# Bryan.net
KiCad netlist of a schematic drawn in EAGLE
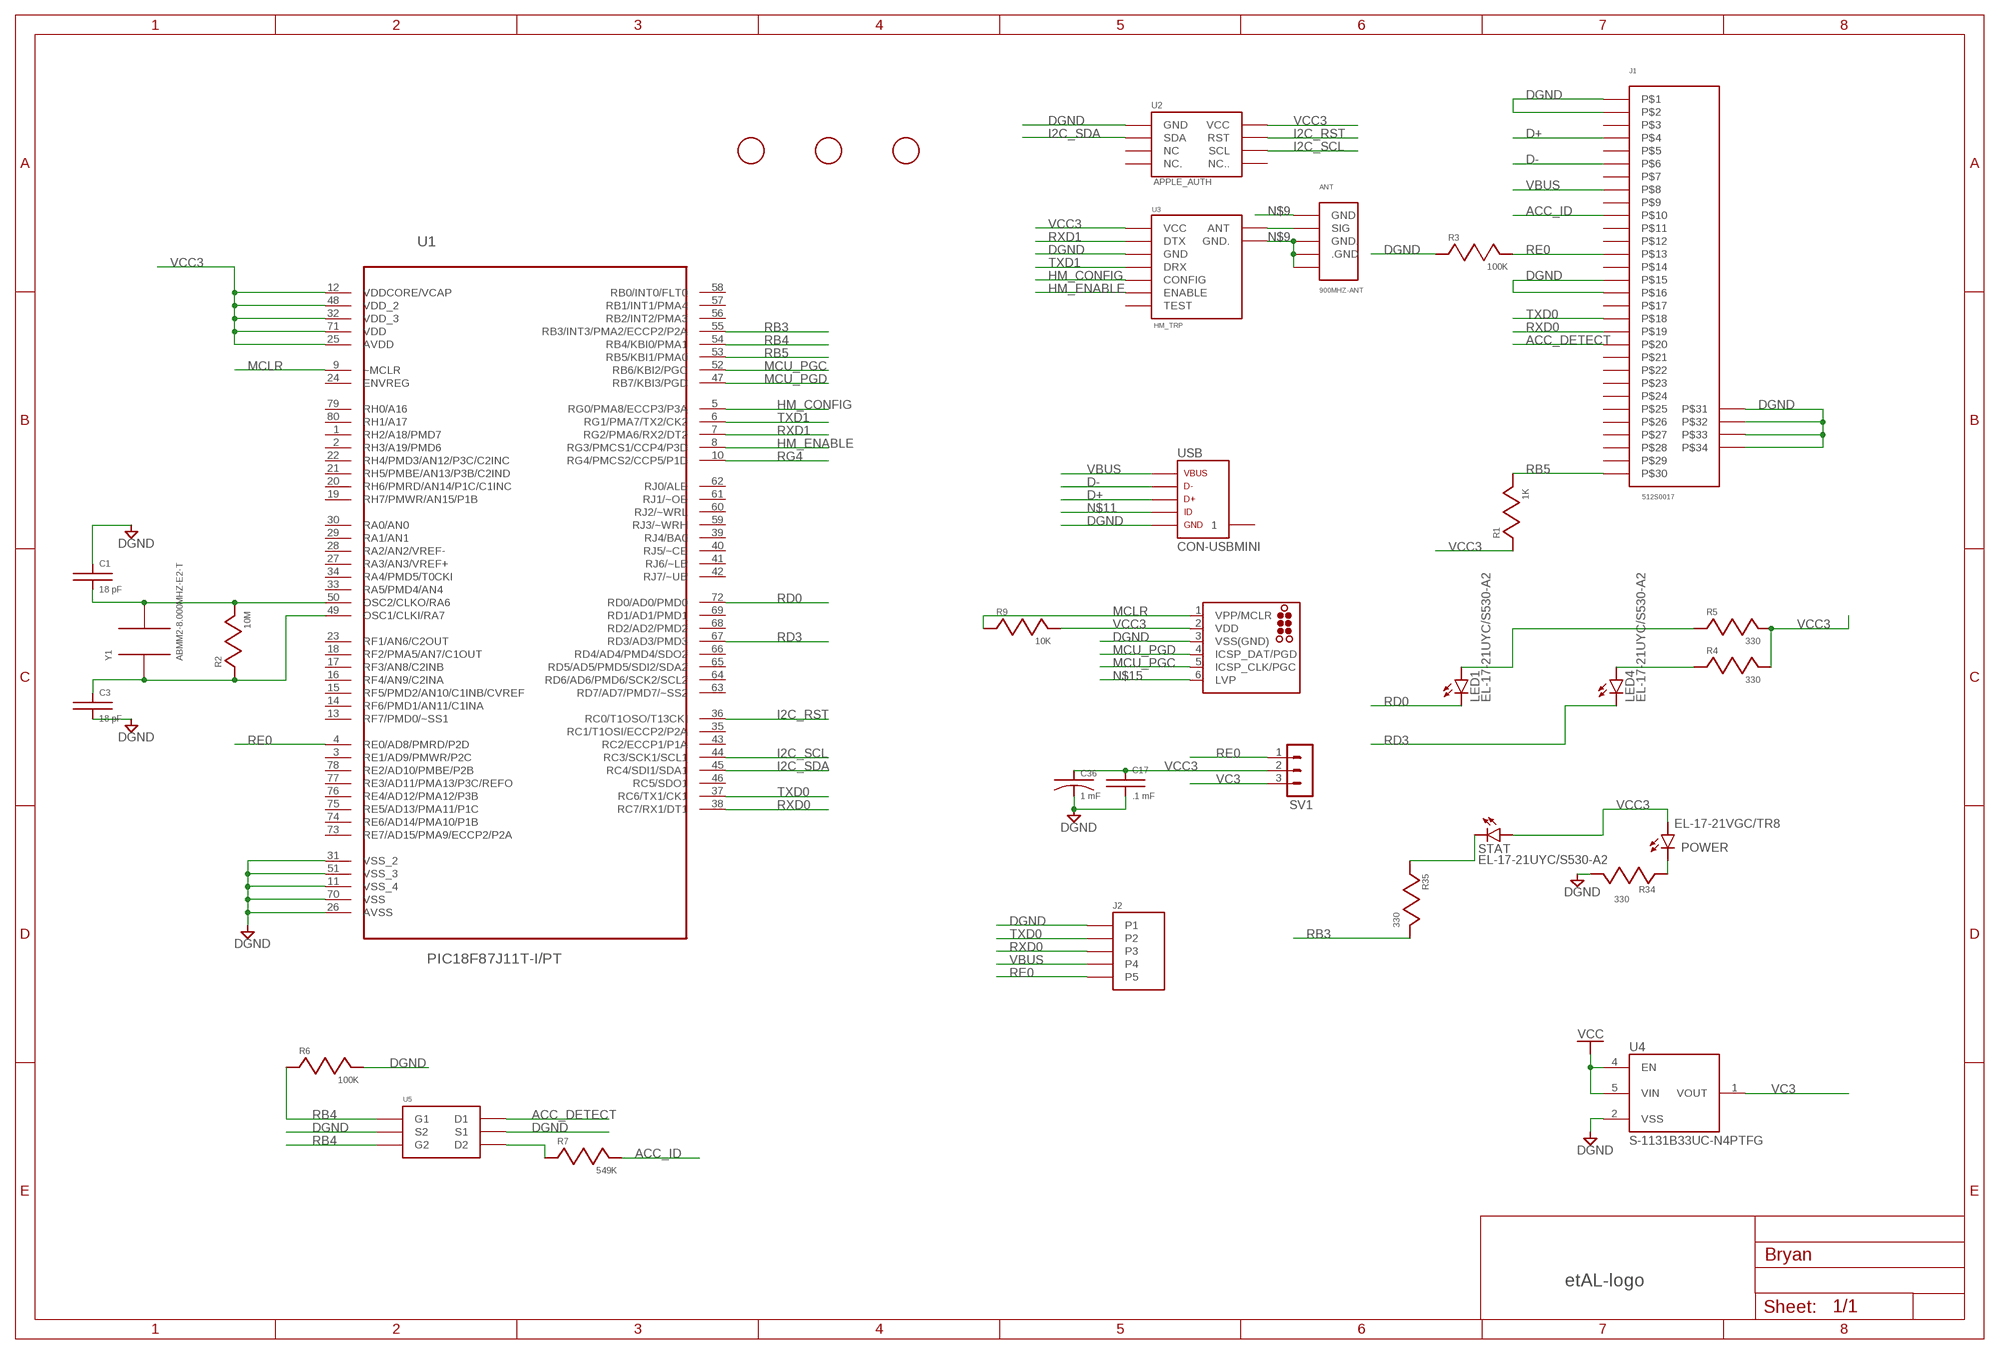
[diagram p0: schematic, sheet 1]

(export (version "E")
  (design (tool "Eeschema 10.0.6"))
  (components
    (comp (ref "ANT")
      (value "900MHZ-ANT")
      (footprint "eagle-import:900MHZ-ANT")
      (libsource (lib "eagle-import") (part "900MHZ-ANT"))
    )
    (comp (ref "C1")
      (value "18 pF")
      (footprint "eagle-import:0603")
      (libsource (lib "eagle-import") (part "C"))
    )
    (comp (ref "C3")
      (value "18 pF")
      (footprint "eagle-import:0603")
      (libsource (lib "eagle-import") (part "C"))
    )
    (comp (ref "C17")
      (value ".1 mF")
      (footprint "eagle-import:0603")
      (libsource (lib "eagle-import") (part "C"))
    )
    (comp (ref "C36")
      (value "1 mF")
      (footprint "eagle-import:1206-LONG")
      (libsource (lib "eagle-import") (part "C-POLAR1206"))
    )
    (comp (ref "J1")
      (value "512S0017")
      (footprint "eagle-import:512S0017")
      (libsource (lib "eagle-import") (part "512S0017"))
    )
    (comp (ref "J2")
      (value "LIGHTNING_C11")
      (footprint "eagle-import:LIGHTNING_C11")
      (libsource (lib "eagle-import") (part "LIGHTNING_C11"))
    )
    (comp (ref "J3")
      (value "TC2030-MCP")
      (footprint "eagle-import:TC2030-MCP")
      (libsource (lib "eagle-import") (part "TC2030-MCP"))
    )
    (comp (ref "LED1")
      (value "EL-17-21UYC/S530-A2")
      (footprint "eagle-import:DIODE-0804")
      (libsource (lib "eagle-import") (part "LED"))
    )
    (comp (ref "LED4")
      (value "EL-17-21UYC/S530-A2")
      (footprint "eagle-import:DIODE-0804")
      (libsource (lib "eagle-import") (part "LED"))
    )
    (comp (ref "POWER")
      (value "EL-17-21VGC/TR8")
      (footprint "eagle-import:DIODE-0804")
      (libsource (lib "eagle-import") (part "LED"))
    )
    (comp (ref "R1") (value "1K") (footprint "eagle-import:0603") (libsource (lib "eagle-import") (part "R")))
    (comp (ref "R2")
      (value "10M")
      (footprint "eagle-import:0603")
      (libsource (lib "eagle-import") (part "R"))
    )
    (comp (ref "R3")
      (value "100K")
      (footprint "eagle-import:0603")
      (libsource (lib "eagle-import") (part "R"))
    )
    (comp (ref "R4")
      (value "330")
      (footprint "eagle-import:0603")
      (libsource (lib "eagle-import") (part "R"))
    )
    (comp (ref "R5")
      (value "330")
      (footprint "eagle-import:0603")
      (libsource (lib "eagle-import") (part "R"))
    )
    (comp (ref "R6")
      (value "100K")
      (footprint "eagle-import:0603")
      (libsource (lib "eagle-import") (part "R"))
    )
    (comp (ref "R7")
      (value "549K")
      (footprint "eagle-import:0603")
      (libsource (lib "eagle-import") (part "R"))
    )
    (comp (ref "R9")
      (value "10K")
      (footprint "eagle-import:0603")
      (libsource (lib "eagle-import") (part "R"))
    )
    (comp (ref "R34")
      (value "330")
      (footprint "eagle-import:0603")
      (libsource (lib "eagle-import") (part "R"))
    )
    (comp (ref "R35")
      (value "330")
      (footprint "eagle-import:0603")
      (libsource (lib "eagle-import") (part "R"))
    )
    (comp (ref "STAT")
      (value "EL-17-21UYC/S530-A2")
      (footprint "eagle-import:DIODE-0804")
      (libsource (lib "eagle-import") (part "LED"))
    )
    (comp (ref "SV1")
      (value "MA03-1")
      (footprint "eagle-import:MA03-1")
      (libsource (lib "eagle-import") (part "MA03-1"))
    )
    (comp (ref "U$1")
      (value "FIDUCIAL")
      (footprint "eagle-import:FIDUCIAL")
      (libsource (lib "eagle-import") (part "FIDUCIAL"))
    )
    (comp (ref "U$2")
      (value "ETAL-LOGO")
      (footprint "eagle-import:ETAL-LOGO")
      (libsource (lib "eagle-import") (part "ETAL-LOGO"))
    )
    (comp (ref "U$3")
      (value "FIDUCIAL")
      (footprint "eagle-import:FIDUCIAL")
      (libsource (lib "eagle-import") (part "FIDUCIAL"))
    )
    (comp (ref "U$4")
      (value "FIDUCIAL")
      (footprint "eagle-import:FIDUCIAL")
      (libsource (lib "eagle-import") (part "FIDUCIAL"))
    )
    (comp (ref "U1")
      (value "PIC18F87J11T-I/PT")
      (footprint "eagle-import:QFP50P1400X1400X120-80N")
      (libsource (lib "eagle-import") (part "PIC18F87J11T-I/PT"))
    )
    (comp (ref "U2")
      (value "APPLE_AUTH")
      (footprint "eagle-import:APPLE_AUTH")
      (libsource (lib "eagle-import") (part "APPLE_AUTH"))
    )
    (comp (ref "U3")
      (value "HM_TRP")
      (footprint "eagle-import:HM-TRP")
      (libsource (lib "eagle-import") (part "HM_TRP"))
    )
    (comp (ref "U4")
      (value "S-1131B33UC-N4PTFG")
      (footprint "eagle-import:SOT-89-5")
      (libsource (lib "eagle-import") (part "S1131"))
    )
    (comp (ref "U5")
      (value "FDC6301N")
      (footprint "eagle-import:SUPER_SOT_6")
      (libsource (lib "eagle-import") (part "FDC6301N"))
    )
    (comp (ref "USB")
      (value "CON-USBMINI")
      (footprint "eagle-import:USBMINI")
      (libsource (lib "eagle-import") (part "CON-USBMINI"))
    )
    (comp (ref "Y1")
      (value "ABMM2-8.000MHZ-E2-T")
      (footprint "eagle-import:CRYSTAL-6X3")
      (libsource (lib "eagle-import") (part "CRYSTAL-ABMM"))
    )
  )
  (nets
    (net (code "1") (name "/ACC_DETECT") (class "Default")
      (node (ref "J1") (pin "P$20") (pinfunction "P$20_P$20") (pintype "bidirectional"))
      (node (ref "U5") (pin "P$6") (pinfunction "D1_P$6") (pintype "bidirectional"))
    )
    (net (code "2") (name "/ACC_ID") (class "Default")
      (node (ref "J1") (pin "P$10") (pinfunction "P$10_P$10") (pintype "bidirectional"))
      (node (ref "R7") (pin "2") (pinfunction "P$2_2") (pintype "bidirectional"))
    )
    (net (code "3") (name "/D+") (class "Default")
      (node (ref "J1") (pin "P$4") (pinfunction "P$4_P$4") (pintype "bidirectional"))
      (node (ref "USB") (pin "D+") (pinfunction "D+_D+") (pintype "bidirectional"))
    )
    (net (code "4") (name "/D-") (class "Default")
      (node (ref "J1") (pin "P$6") (pinfunction "P$6_P$6") (pintype "bidirectional"))
      (node (ref "USB") (pin "D-") (pinfunction "D-_D-") (pintype "bidirectional"))
    )
    (net (code "5") (name "/HM_CONFIG") (class "Default")
      (node (ref "U1") (pin "5") (pinfunction "RG0/PMA8/ECCP3/P3A_5") (pintype "bidirectional"))
      (node (ref "U3") (pin "P5") (pinfunction "CONFIG_P5") (pintype "bidirectional"))
    )
    (net (code "6") (name "/HM_ENABLE") (class "Default")
      (node (ref "U1") (pin "8") (pinfunction "RG3/PMCS1/CCP4/P3D_8") (pintype "bidirectional"))
      (node (ref "U3") (pin "P6") (pinfunction "ENABLE_P6") (pintype "bidirectional"))
    )
    (net (code "7") (name "/I2C_RST") (class "Default")
      (node (ref "U1") (pin "36") (pinfunction "RC0/T1OSO/T13CKI_36") (pintype "bidirectional"))
      (node (ref "U2") (pin "P$7") (pinfunction "RST_P$7") (pintype "bidirectional"))
    )
    (net (code "8") (name "/I2C_SCL") (class "Default")
      (node (ref "U1") (pin "44") (pinfunction "RC3/SCK1/SCL1_44") (pintype "bidirectional"))
      (node (ref "U2") (pin "P$6") (pinfunction "SCL_P$6") (pintype "bidirectional"))
    )
    (net (code "9") (name "/I2C_SDA") (class "Default")
      (node (ref "U1") (pin "45") (pinfunction "RC4/SDI1/SDA1_45") (pintype "bidirectional"))
      (node (ref "U2") (pin "P$2") (pinfunction "SDA_P$2") (pintype "bidirectional"))
    )
    (net (code "10") (name "/MCLR") (class "Default")
      (node (ref "J3") (pin "1") (pinfunction "VPP/MCLR_1") (pintype "passive"))
      (node (ref "R9") (pin "1") (pinfunction "P$1_1") (pintype "bidirectional"))
      (node (ref "U1") (pin "9") (pinfunction "~{MCLR}_9") (pintype "input"))
    )
    (net (code "11") (name "/MCU_PGC") (class "Default")
      (node (ref "J3") (pin "5") (pinfunction "ICSP_CLK/PGC_5") (pintype "output"))
      (node (ref "U1") (pin "52") (pinfunction "RB6/KBI2/PGC_52") (pintype "bidirectional"))
    )
    (net (code "12") (name "/MCU_PGD") (class "Default")
      (node (ref "J3") (pin "4") (pinfunction "ICSP_DAT/PGD_4") (pintype "bidirectional"))
      (node (ref "U1") (pin "47") (pinfunction "RB7/KBI3/PGD_47") (pintype "bidirectional"))
    )
    (net (code "13") (name "/N$9") (class "Default")
      (node (ref "ANT") (pin "P$1") (pinfunction ".GND_P$1") (pintype "bidirectional"))
      (node (ref "ANT") (pin "P$3") (pinfunction "GND._P$3") (pintype "bidirectional"))
      (node (ref "ANT") (pin "P$4") (pinfunction "GND_P$4") (pintype "bidirectional"))
      (node (ref "ANT") (pin "P$5") (pintype "bidirectional"))
      (node (ref "U3") (pin "P8") (pinfunction "GND._P8") (pintype "bidirectional"))
    )
    (net (code "14") (name "/N$11") (class "Default")
      (node (ref "USB") (pin "ID") (pinfunction "ID_ID") (pintype "bidirectional"))
    )
    (net (code "15") (name "/N$15") (class "Default")
      (node (ref "J3") (pin "6") (pinfunction "LVP_6") (pintype "bidirectional"))
    )
    (net (code "16") (name "/RB3") (class "Default")
      (node (ref "R35") (pin "2") (pinfunction "P$2_2") (pintype "bidirectional"))
      (node (ref "U1") (pin "55") (pinfunction "RB3/INT3/PMA2/ECCP2/P2A_55") (pintype "bidirectional"))
    )
    (net (code "17") (name "/RB4") (class "Default")
      (node (ref "R6") (pin "1") (pinfunction "P$1_1") (pintype "bidirectional"))
      (node (ref "U1") (pin "54") (pinfunction "RB4/KBI0/PMA1_54") (pintype "bidirectional"))
      (node (ref "U5") (pin "P$1") (pinfunction "G1_P$1") (pintype "bidirectional"))
      (node (ref "U5") (pin "P$3") (pinfunction "G2_P$3") (pintype "bidirectional"))
    )
    (net (code "18") (name "/RB5") (class "Default")
      (node (ref "J1") (pin "P$30") (pinfunction "P$30_P$30") (pintype "bidirectional"))
      (node (ref "R1") (pin "2") (pinfunction "P$2_2") (pintype "bidirectional"))
      (node (ref "U1") (pin "53") (pinfunction "RB5/KBI1/PMA0_53") (pintype "bidirectional"))
    )
    (net (code "19") (name "/RD0") (class "Default")
      (node (ref "LED1") (pin "ANODE") (pinfunction "ANODE_ANODE") (pintype "passive"))
      (node (ref "U1") (pin "72") (pinfunction "RD0/AD0/PMD0_72") (pintype "bidirectional"))
    )
    (net (code "20") (name "/RD3") (class "Default")
      (node (ref "LED4") (pin "ANODE") (pinfunction "ANODE_ANODE") (pintype "passive"))
      (node (ref "U1") (pin "67") (pinfunction "RD3/AD3/PMD3_67") (pintype "bidirectional"))
    )
    (net (code "21") (name "/RE0") (class "Default")
      (node (ref "J1") (pin "P$13") (pinfunction "P$13_P$13") (pintype "bidirectional"))
      (node (ref "J2") (pin "P5") (pinfunction "P5_P5") (pintype "bidirectional"))
      (node (ref "R3") (pin "2") (pinfunction "P$2_2") (pintype "bidirectional"))
      (node (ref "SV1") (pin "1") (pinfunction "1_1") (pintype "passive"))
      (node (ref "U1") (pin "4") (pinfunction "RE0/AD8/PMRD/P2D_4") (pintype "bidirectional"))
    )
    (net (code "22") (name "/RG4") (class "Default")
      (node (ref "U1") (pin "10") (pinfunction "RG4/PMCS2/CCP5/P1D_10") (pintype "bidirectional"))
    )
    (net (code "23") (name "/RXD0") (class "Default")
      (node (ref "J1") (pin "P$19") (pinfunction "P$19_P$19") (pintype "bidirectional"))
      (node (ref "J2") (pin "P3") (pinfunction "P3_P3") (pintype "bidirectional"))
      (node (ref "U1") (pin "38") (pinfunction "RC7/RX1/DT1_38") (pintype "bidirectional"))
    )
    (net (code "24") (name "/RXD1") (class "Default")
      (node (ref "U1") (pin "7") (pinfunction "RG2/PMA6/RX2/DT2_7") (pintype "bidirectional"))
      (node (ref "U3") (pin "P2") (pinfunction "DTX_P2") (pintype "bidirectional"))
    )
    (net (code "25") (name "/TXD0") (class "Default")
      (node (ref "J1") (pin "P$18") (pinfunction "P$18_P$18") (pintype "bidirectional"))
      (node (ref "J2") (pin "P2") (pinfunction "P2_P2") (pintype "bidirectional"))
      (node (ref "U1") (pin "37") (pinfunction "RC6/TX1/CK1_37") (pintype "bidirectional"))
    )
    (net (code "26") (name "/TXD1") (class "Default")
      (node (ref "U1") (pin "6") (pinfunction "RG1/PMA7/TX2/CK2_6") (pintype "bidirectional"))
      (node (ref "U3") (pin "P4") (pinfunction "DRX_P4") (pintype "bidirectional"))
    )
    (net (code "27") (name "/VBUS") (class "Default")
      (node (ref "J1") (pin "P$8") (pinfunction "P$8_P$8") (pintype "bidirectional"))
      (node (ref "J2") (pin "P4") (pinfunction "P4_P4") (pintype "bidirectional"))
      (node (ref "USB") (pin "VBUS") (pinfunction "VBUS_VBUS") (pintype "bidirectional"))
    )
    (net (code "28") (name "/VC3") (class "Default")
      (node (ref "SV1") (pin "3") (pinfunction "3_3") (pintype "passive"))
      (node (ref "U4") (pin "1") (pinfunction "VOUT_1") (pintype "bidirectional"))
    )
    (net (code "29") (name "/VCC3") (class "Default")
      (node (ref "C17") (pin "1") (pinfunction "P$1_1") (pintype "bidirectional"))
      (node (ref "C36") (pin "2") (pinfunction "CATHODE_2") (pintype "bidirectional"))
      (node (ref "J3") (pin "2") (pinfunction "VDD_2") (pintype "bidirectional"))
      (node (ref "POWER") (pin "CATHODE") (pinfunction "CATHODE_CATHODE") (pintype "passive"))
      (node (ref "R1") (pin "1") (pinfunction "P$1_1") (pintype "bidirectional"))
      (node (ref "R4") (pin "2") (pinfunction "P$2_2") (pintype "bidirectional"))
      (node (ref "R5") (pin "2") (pinfunction "P$2_2") (pintype "bidirectional"))
      (node (ref "R9") (pin "2") (pinfunction "P$2_2") (pintype "bidirectional"))
      (node (ref "STAT") (pin "CATHODE") (pinfunction "CATHODE_CATHODE") (pintype "passive"))
      (node (ref "SV1") (pin "2") (pinfunction "2_2") (pintype "passive"))
      (node (ref "U1") (pin "12") (pinfunction "VDDCORE/VCAP_12") (pintype "power_in"))
      (node (ref "U1") (pin "25") (pinfunction "AVDD_25") (pintype "power_in"))
      (node (ref "U1") (pin "32") (pinfunction "VDD_3_32") (pintype "power_in"))
      (node (ref "U1") (pin "48") (pinfunction "VDD_2_48") (pintype "power_in"))
      (node (ref "U1") (pin "71") (pinfunction "VDD_71") (pintype "power_in"))
      (node (ref "U2") (pin "P$8") (pinfunction "VCC_P$8") (pintype "bidirectional"))
      (node (ref "U3") (pin "P1") (pinfunction "VCC_P1") (pintype "bidirectional"))
    )
    (net (code "30") (name "DGND") (class "Default")
      (node (ref "C1") (pin "1") (pinfunction "P$1_1") (pintype "bidirectional"))
      (node (ref "C17") (pin "2") (pinfunction "P$2_2") (pintype "bidirectional"))
      (node (ref "C3") (pin "2") (pinfunction "P$2_2") (pintype "bidirectional"))
      (node (ref "C36") (pin "1") (pinfunction "ANODE_1") (pintype "bidirectional"))
      (node (ref "J1") (pin "P$1") (pinfunction "P$1_P$1") (pintype "bidirectional"))
      (node (ref "J1") (pin "P$15") (pinfunction "P$15_P$15") (pintype "bidirectional"))
      (node (ref "J1") (pin "P$16") (pinfunction "P$16_P$16") (pintype "bidirectional"))
      (node (ref "J1") (pin "P$2") (pinfunction "P$2_P$2") (pintype "bidirectional"))
      (node (ref "J1") (pin "P$31") (pinfunction "P$31_P$31") (pintype "bidirectional"))
      (node (ref "J1") (pin "P$32") (pinfunction "P$32_P$32") (pintype "bidirectional"))
      (node (ref "J1") (pin "P$33") (pinfunction "P$33_P$33") (pintype "bidirectional"))
      (node (ref "J1") (pin "P$34") (pinfunction "P$34_P$34") (pintype "bidirectional"))
      (node (ref "J2") (pin "P1") (pinfunction "P1_P1") (pintype "bidirectional"))
      (node (ref "J3") (pin "3") (pinfunction "VSS(GND)_3") (pintype "bidirectional"))
      (node (ref "R3") (pin "1") (pinfunction "P$1_1") (pintype "bidirectional"))
      (node (ref "R34") (pin "2") (pinfunction "P$2_2") (pintype "bidirectional"))
      (node (ref "R6") (pin "2") (pinfunction "P$2_2") (pintype "bidirectional"))
      (node (ref "U1") (pin "11") (pinfunction "VSS_4_11") (pintype "power_in"))
      (node (ref "U1") (pin "26") (pinfunction "AVSS_26") (pintype "power_in"))
      (node (ref "U1") (pin "31") (pinfunction "VSS_2_31") (pintype "power_in"))
      (node (ref "U1") (pin "51") (pinfunction "VSS_3_51") (pintype "power_in"))
      (node (ref "U1") (pin "70") (pinfunction "VSS_70") (pintype "power_in"))
      (node (ref "U2") (pin "P$1") (pinfunction "GND_P$1") (pintype "bidirectional"))
      (node (ref "U3") (pin "P3") (pinfunction "GND_P3") (pintype "bidirectional"))
      (node (ref "U4") (pin "2") (pinfunction "VSS_2") (pintype "bidirectional"))
      (node (ref "U5") (pin "P$2") (pinfunction "S2_P$2") (pintype "bidirectional"))
      (node (ref "U5") (pin "P$5") (pinfunction "S1_P$5") (pintype "bidirectional"))
      (node (ref "USB") (pin "GND") (pinfunction "GND_GND") (pintype "bidirectional"))
    )
    (net (code "31") (name "Net-(ANT-SIG)") (class "Default")
      (node (ref "ANT") (pin "P$2") (pinfunction "SIG_P$2") (pintype "bidirectional"))
      (node (ref "U3") (pin "P9") (pinfunction "ANT_P9") (pintype "bidirectional"))
    )
    (net (code "32") (name "Net-(C1-P$2)") (class "Default")
      (node (ref "C1") (pin "2") (pinfunction "P$2_2") (pintype "bidirectional"))
      (node (ref "R2") (pin "2") (pinfunction "P$2_2") (pintype "bidirectional"))
      (node (ref "U1") (pin "50") (pinfunction "OSC2/CLKO/RA6_50") (pintype "bidirectional"))
      (node (ref "Y1") (pin "P$3") (pinfunction "2_P$3") (pintype "bidirectional"))
    )
    (net (code "33") (name "Net-(C3-P$1)") (class "Default")
      (node (ref "C3") (pin "1") (pinfunction "P$1_1") (pintype "bidirectional"))
      (node (ref "R2") (pin "1") (pinfunction "P$1_1") (pintype "bidirectional"))
      (node (ref "U1") (pin "49") (pinfunction "OSC1/CLKI/RA7_49") (pintype "bidirectional"))
      (node (ref "Y1") (pin "P$1") (pinfunction "1_P$1") (pintype "bidirectional"))
    )
    (net (code "34") (name "Net-(R4-P$1)") (class "Default")
      (node (ref "LED4") (pin "CATHODE") (pinfunction "CATHODE_CATHODE") (pintype "passive"))
      (node (ref "R4") (pin "1") (pinfunction "P$1_1") (pintype "bidirectional"))
    )
    (net (code "35") (name "Net-(R5-P$1)") (class "Default")
      (node (ref "LED1") (pin "CATHODE") (pinfunction "CATHODE_CATHODE") (pintype "passive"))
      (node (ref "R5") (pin "1") (pinfunction "P$1_1") (pintype "bidirectional"))
    )
    (net (code "36") (name "Net-(R7-P$1)") (class "Default")
      (node (ref "R7") (pin "1") (pinfunction "P$1_1") (pintype "bidirectional"))
      (node (ref "U5") (pin "P$4") (pinfunction "D2_P$4") (pintype "bidirectional"))
    )
    (net (code "37") (name "Net-(R34-P$1)") (class "Default")
      (node (ref "POWER") (pin "ANODE") (pinfunction "ANODE_ANODE") (pintype "passive"))
      (node (ref "R34") (pin "1") (pinfunction "P$1_1") (pintype "bidirectional"))
    )
    (net (code "38") (name "Net-(R35-P$1)") (class "Default")
      (node (ref "R35") (pin "1") (pinfunction "P$1_1") (pintype "bidirectional"))
      (node (ref "STAT") (pin "ANODE") (pinfunction "ANODE_ANODE") (pintype "passive"))
    )
    (net (code "39") (name "VCC") (class "Default")
      (node (ref "U4") (pin "4") (pinfunction "EN_4") (pintype "bidirectional"))
      (node (ref "U4") (pin "5") (pinfunction "VIN_5") (pintype "bidirectional"))
    )
    (net (code "40") (name "unconnected-(J1-PadP$3)") (class "Default")
      (node (ref "J1") (pin "P$3") (pinfunction "P$3_P$3") (pintype "bidirectional"))
    )
    (net (code "41") (name "unconnected-(J1-PadP$5)") (class "Default")
      (node (ref "J1") (pin "P$5") (pinfunction "P$5_P$5") (pintype "bidirectional"))
    )
    (net (code "42") (name "unconnected-(J1-PadP$7)") (class "Default")
      (node (ref "J1") (pin "P$7") (pinfunction "P$7_P$7") (pintype "bidirectional"))
    )
    (net (code "43") (name "unconnected-(J1-PadP$9)") (class "Default")
      (node (ref "J1") (pin "P$9") (pinfunction "P$9_P$9") (pintype "bidirectional"))
    )
    (net (code "44") (name "unconnected-(J1-PadP$11)") (class "Default")
      (node (ref "J1") (pin "P$11") (pinfunction "P$11_P$11") (pintype "bidirectional"))
    )
    (net (code "45") (name "unconnected-(J1-PadP$12)") (class "Default")
      (node (ref "J1") (pin "P$12") (pinfunction "P$12_P$12") (pintype "bidirectional"))
    )
    (net (code "46") (name "unconnected-(J1-PadP$14)") (class "Default")
      (node (ref "J1") (pin "P$14") (pinfunction "P$14_P$14") (pintype "bidirectional"))
    )
    (net (code "47") (name "unconnected-(J1-PadP$17)") (class "Default")
      (node (ref "J1") (pin "P$17") (pinfunction "P$17_P$17") (pintype "bidirectional"))
    )
    (net (code "48") (name "unconnected-(J1-PadP$21)") (class "Default")
      (node (ref "J1") (pin "P$21") (pinfunction "P$21_P$21") (pintype "bidirectional"))
    )
    (net (code "49") (name "unconnected-(J1-PadP$22)") (class "Default")
      (node (ref "J1") (pin "P$22") (pinfunction "P$22_P$22") (pintype "bidirectional"))
    )
    (net (code "50") (name "unconnected-(J1-PadP$23)") (class "Default")
      (node (ref "J1") (pin "P$23") (pinfunction "P$23_P$23") (pintype "bidirectional"))
    )
    (net (code "51") (name "unconnected-(J1-PadP$24)") (class "Default")
      (node (ref "J1") (pin "P$24") (pinfunction "P$24_P$24") (pintype "bidirectional"))
    )
    (net (code "52") (name "unconnected-(J1-PadP$25)") (class "Default")
      (node (ref "J1") (pin "P$25") (pinfunction "P$25_P$25") (pintype "bidirectional"))
    )
    (net (code "53") (name "unconnected-(J1-PadP$26)") (class "Default")
      (node (ref "J1") (pin "P$26") (pinfunction "P$26_P$26") (pintype "bidirectional"))
    )
    (net (code "54") (name "unconnected-(J1-PadP$27)") (class "Default")
      (node (ref "J1") (pin "P$27") (pinfunction "P$27_P$27") (pintype "bidirectional"))
    )
    (net (code "55") (name "unconnected-(J1-PadP$28)") (class "Default")
      (node (ref "J1") (pin "P$28") (pinfunction "P$28_P$28") (pintype "bidirectional"))
    )
    (net (code "56") (name "unconnected-(J1-PadP$29)") (class "Default")
      (node (ref "J1") (pin "P$29") (pinfunction "P$29_P$29") (pintype "bidirectional"))
    )
    (net (code "57") (name "unconnected-(U1-ENVREG-Pad24)") (class "Default")
      (node (ref "U1") (pin "24") (pinfunction "ENVREG_24") (pintype "input"))
    )
    (net (code "58") (name "unconnected-(U1-RA0{slash}AN0-Pad30)") (class "Default")
      (node (ref "U1") (pin "30") (pinfunction "RA0/AN0_30") (pintype "bidirectional"))
    )
    (net (code "59") (name "unconnected-(U1-RA1{slash}AN1-Pad29)") (class "Default")
      (node (ref "U1") (pin "29") (pinfunction "RA1/AN1_29") (pintype "bidirectional"))
    )
    (net (code "60") (name "unconnected-(U1-RA2{slash}AN2{slash}VREF--Pad28)") (class "Default")
      (node (ref "U1") (pin "28") (pinfunction "RA2/AN2/VREF-_28") (pintype "bidirectional"))
    )
    (net (code "61") (name "unconnected-(U1-RA3{slash}AN3{slash}VREF+-Pad27)") (class "Default")
      (node (ref "U1") (pin "27") (pinfunction "RA3/AN3/VREF+_27") (pintype "bidirectional"))
    )
    (net (code "62") (name "unconnected-(U1-RA4{slash}PMD5{slash}T0CKI-Pad34)") (class "Default")
      (node (ref "U1") (pin "34") (pinfunction "RA4/PMD5/T0CKI_34") (pintype "bidirectional"))
    )
    (net (code "63") (name "unconnected-(U1-RA5{slash}PMD4{slash}AN4-Pad33)") (class "Default")
      (node (ref "U1") (pin "33") (pinfunction "RA5/PMD4/AN4_33") (pintype "bidirectional"))
    )
    (net (code "64") (name "unconnected-(U1-RB0{slash}INT0{slash}FLT0-Pad58)") (class "Default")
      (node (ref "U1") (pin "58") (pinfunction "RB0/INT0/FLT0_58") (pintype "bidirectional"))
    )
    (net (code "65") (name "unconnected-(U1-RB1{slash}INT1{slash}PMA4-Pad57)") (class "Default")
      (node (ref "U1") (pin "57") (pinfunction "RB1/INT1/PMA4_57") (pintype "bidirectional"))
    )
    (net (code "66") (name "unconnected-(U1-RB2{slash}INT2{slash}PMA3-Pad56)") (class "Default")
      (node (ref "U1") (pin "56") (pinfunction "RB2/INT2/PMA3_56") (pintype "bidirectional"))
    )
    (net (code "67") (name "unconnected-(U1-RC1{slash}T1OSI{slash}ECCP2{slash}P2A-Pad35)") (class "Default")
      (node (ref "U1") (pin "35") (pinfunction "RC1/T1OSI/ECCP2/P2A_35") (pintype "bidirectional"))
    )
    (net (code "68") (name "unconnected-(U1-RC2{slash}ECCP1{slash}P1A-Pad43)") (class "Default")
      (node (ref "U1") (pin "43") (pinfunction "RC2/ECCP1/P1A_43") (pintype "bidirectional"))
    )
    (net (code "69") (name "unconnected-(U1-RC5{slash}SDO1-Pad46)") (class "Default")
      (node (ref "U1") (pin "46") (pinfunction "RC5/SDO1_46") (pintype "bidirectional"))
    )
    (net (code "70") (name "unconnected-(U1-RD1{slash}AD1{slash}PMD1-Pad69)") (class "Default")
      (node (ref "U1") (pin "69") (pinfunction "RD1/AD1/PMD1_69") (pintype "bidirectional"))
    )
    (net (code "71") (name "unconnected-(U1-RD2{slash}AD2{slash}PMD2-Pad68)") (class "Default")
      (node (ref "U1") (pin "68") (pinfunction "RD2/AD2/PMD2_68") (pintype "bidirectional"))
    )
    (net (code "72") (name "unconnected-(U1-RD4{slash}AD4{slash}PMD4{slash}SDO2-Pad66)") (class "Default")
      (node (ref "U1") (pin "66") (pinfunction "RD4/AD4/PMD4/SDO2_66") (pintype "bidirectional"))
    )
    (net (code "73") (name "unconnected-(U1-RD5{slash}AD5{slash}PMD5{slash}SDI2{slash}SDA2-Pad65)") (class "Default")
      (node (ref "U1") (pin "65") (pinfunction "RD5/AD5/PMD5/SDI2/SDA2_65") (pintype "bidirectional"))
    )
    (net (code "74") (name "unconnected-(U1-RD6{slash}AD6{slash}PMD6{slash}SCK2{slash}SCL2-Pad64)") (class "Default")
      (node (ref "U1") (pin "64") (pinfunction "RD6/AD6/PMD6/SCK2/SCL2_64") (pintype "bidirectional"))
    )
    (net (code "75") (name "unconnected-(U1-RD7{slash}AD7{slash}PMD7{slash}~{SS2}-Pad63)") (class "Default")
      (node (ref "U1") (pin "63") (pinfunction "RD7/AD7/PMD7/~{SS2}_63") (pintype "bidirectional"))
    )
    (net (code "76") (name "unconnected-(U1-RE1{slash}AD9{slash}PMWR{slash}P2C-Pad3)") (class "Default")
      (node (ref "U1") (pin "3") (pinfunction "RE1/AD9/PMWR/P2C_3") (pintype "bidirectional"))
    )
    (net (code "77") (name "unconnected-(U1-RE2{slash}AD10{slash}PMBE{slash}P2B-Pad78)") (class "Default")
      (node (ref "U1") (pin "78") (pinfunction "RE2/AD10/PMBE/P2B_78") (pintype "bidirectional"))
    )
    (net (code "78") (name "unconnected-(U1-RE3{slash}AD11{slash}PMA13{slash}P3C{slash}REFO-Pad77)") (class "Default")
      (node (ref "U1") (pin "77") (pinfunction "RE3/AD11/PMA13/P3C/REFO_77") (pintype "bidirectional"))
    )
    (net (code "79") (name "unconnected-(U1-RE4{slash}AD12{slash}PMA12{slash}P3B-Pad76)") (class "Default")
      (node (ref "U1") (pin "76") (pinfunction "RE4/AD12/PMA12/P3B_76") (pintype "bidirectional"))
    )
    (net (code "80") (name "unconnected-(U1-RE5{slash}AD13{slash}PMA11{slash}P1C-Pad75)") (class "Default")
      (node (ref "U1") (pin "75") (pinfunction "RE5/AD13/PMA11/P1C_75") (pintype "bidirectional"))
    )
    (net (code "81") (name "unconnected-(U1-RE6{slash}AD14{slash}PMA10{slash}P1B-Pad74)") (class "Default")
      (node (ref "U1") (pin "74") (pinfunction "RE6/AD14/PMA10/P1B_74") (pintype "bidirectional"))
    )
    (net (code "82") (name "unconnected-(U1-RE7{slash}AD15{slash}PMA9{slash}ECCP2{slash}P2A-Pad73)") (class "Default")
      (node (ref "U1") (pin "73") (pinfunction "RE7/AD15/PMA9/ECCP2/P2A_73") (pintype "bidirectional"))
    )
    (net (code "83") (name "unconnected-(U1-RF1{slash}AN6{slash}C2OUT-Pad23)") (class "Default")
      (node (ref "U1") (pin "23") (pinfunction "RF1/AN6/C2OUT_23") (pintype "bidirectional"))
    )
    (net (code "84") (name "unconnected-(U1-RF2{slash}PMA5{slash}AN7{slash}C1OUT-Pad18)") (class "Default")
      (node (ref "U1") (pin "18") (pinfunction "RF2/PMA5/AN7/C1OUT_18") (pintype "bidirectional"))
    )
    (net (code "85") (name "unconnected-(U1-RF3{slash}AN8{slash}C2INB-Pad17)") (class "Default")
      (node (ref "U1") (pin "17") (pinfunction "RF3/AN8/C2INB_17") (pintype "bidirectional"))
    )
    (net (code "86") (name "unconnected-(U1-RF4{slash}AN9{slash}C2INA-Pad16)") (class "Default")
      (node (ref "U1") (pin "16") (pinfunction "RF4/AN9/C2INA_16") (pintype "bidirectional"))
    )
    (net (code "87") (name "unconnected-(U1-RF5{slash}PMD2{slash}AN10{slash}C1INB{slash}CVREF-Pad15)") (class "Default")
      (node (ref "U1") (pin "15") (pinfunction "RF5/PMD2/AN10/C1INB/CVREF_15") (pintype "bidirectional"))
    )
    (net (code "88") (name "unconnected-(U1-RF6{slash}PMD1{slash}AN11{slash}C1INA-Pad14)") (class "Default")
      (node (ref "U1") (pin "14") (pinfunction "RF6/PMD1/AN11/C1INA_14") (pintype "bidirectional"))
    )
    (net (code "89") (name "unconnected-(U1-RF7{slash}PMD0{slash}~{SS1}-Pad13)") (class "Default")
      (node (ref "U1") (pin "13") (pinfunction "RF7/PMD0/~{SS1}_13") (pintype "bidirectional"))
    )
    (net (code "90") (name "unconnected-(U1-RH0{slash}A16-Pad79)") (class "Default")
      (node (ref "U1") (pin "79") (pinfunction "RH0/A16_79") (pintype "bidirectional"))
    )
    (net (code "91") (name "unconnected-(U1-RH1{slash}A17-Pad80)") (class "Default")
      (node (ref "U1") (pin "80") (pinfunction "RH1/A17_80") (pintype "bidirectional"))
    )
    (net (code "92") (name "unconnected-(U1-RH2{slash}A18{slash}PMD7-Pad1)") (class "Default")
      (node (ref "U1") (pin "1") (pinfunction "RH2/A18/PMD7_1") (pintype "bidirectional"))
    )
    (net (code "93") (name "unconnected-(U1-RH3{slash}A19{slash}PMD6-Pad2)") (class "Default")
      (node (ref "U1") (pin "2") (pinfunction "RH3/A19/PMD6_2") (pintype "bidirectional"))
    )
    (net (code "94") (name "unconnected-(U1-RH4{slash}PMD3{slash}AN12{slash}P3C{slash}C2INC-Pad22)") (class "Default")
      (node (ref "U1") (pin "22") (pinfunction "RH4/PMD3/AN12/P3C/C2INC_22") (pintype "bidirectional"))
    )
    (net (code "95") (name "unconnected-(U1-RH5{slash}PMBE{slash}AN13{slash}P3B{slash}C2IND-Pad21)") (class "Default")
      (node (ref "U1") (pin "21") (pinfunction "RH5/PMBE/AN13/P3B/C2IND_21") (pintype "bidirectional"))
    )
    (net (code "96") (name "unconnected-(U1-RH6{slash}PMRD{slash}AN14{slash}P1C{slash}C1INC-Pad20)") (class "Default")
      (node (ref "U1") (pin "20") (pinfunction "RH6/PMRD/AN14/P1C/C1INC_20") (pintype "bidirectional"))
    )
    (net (code "97") (name "unconnected-(U1-RH7{slash}PMWR{slash}AN15{slash}P1B-Pad19)") (class "Default")
      (node (ref "U1") (pin "19") (pinfunction "RH7/PMWR/AN15/P1B_19") (pintype "bidirectional"))
    )
    (net (code "98") (name "unconnected-(U1-RJ0{slash}ALE-Pad62)") (class "Default")
      (node (ref "U1") (pin "62") (pinfunction "RJ0/ALE_62") (pintype "bidirectional"))
    )
    (net (code "99") (name "unconnected-(U1-RJ1{slash}~{OE}-Pad61)") (class "Default")
      (node (ref "U1") (pin "61") (pinfunction "RJ1/~{OE}_61") (pintype "bidirectional"))
    )
    (net (code "100") (name "unconnected-(U1-RJ2{slash}~{WRL}-Pad60)") (class "Default")
      (node (ref "U1") (pin "60") (pinfunction "RJ2/~{WRL}_60") (pintype "bidirectional"))
    )
    (net (code "101") (name "unconnected-(U1-RJ3{slash}~{WRH}-Pad59)") (class "Default")
      (node (ref "U1") (pin "59") (pinfunction "RJ3/~{WRH}_59") (pintype "bidirectional"))
    )
    (net (code "102") (name "unconnected-(U1-RJ4{slash}BA0-Pad39)") (class "Default")
      (node (ref "U1") (pin "39") (pinfunction "RJ4/BA0_39") (pintype "bidirectional"))
    )
    (net (code "103") (name "unconnected-(U1-RJ5{slash}~{CE}-Pad40)") (class "Default")
      (node (ref "U1") (pin "40") (pinfunction "RJ5/~{CE}_40") (pintype "bidirectional"))
    )
    (net (code "104") (name "unconnected-(U1-RJ6{slash}~{LB}-Pad41)") (class "Default")
      (node (ref "U1") (pin "41") (pinfunction "RJ6/~{LB}_41") (pintype "bidirectional"))
    )
    (net (code "105") (name "unconnected-(U1-RJ7{slash}~{UB}-Pad42)") (class "Default")
      (node (ref "U1") (pin "42") (pinfunction "RJ7/~{UB}_42") (pintype "bidirectional"))
    )
    (net (code "106") (name "unconnected-(U2-NC-PadP$3)") (class "Default")
      (node (ref "U2") (pin "P$3") (pinfunction "NC_P$3") (pintype "bidirectional"))
    )
    (net (code "107") (name "unconnected-(U2-NC.-PadP$4)") (class "Default")
      (node (ref "U2") (pin "P$4") (pinfunction "NC._P$4") (pintype "bidirectional"))
    )
    (net (code "108") (name "unconnected-(U2-NC..-PadP$5)") (class "Default")
      (node (ref "U2") (pin "P$5") (pinfunction "NC.._P$5") (pintype "bidirectional"))
    )
    (net (code "109") (name "unconnected-(U3-TEST-PadP7)") (class "Default")
      (node (ref "U3") (pin "P7") (pinfunction "TEST_P7") (pintype "bidirectional"))
    )
    (net (code "110") (name "unconnected-(USB-1-PadP$1)") (class "Default")
      (node (ref "USB") (pin "P$1") (pinfunction "1_P$1") (pintype "bidirectional"))
    )
  )
)
